# Control.net
KiCad netlist of a schematic drawn in EAGLE
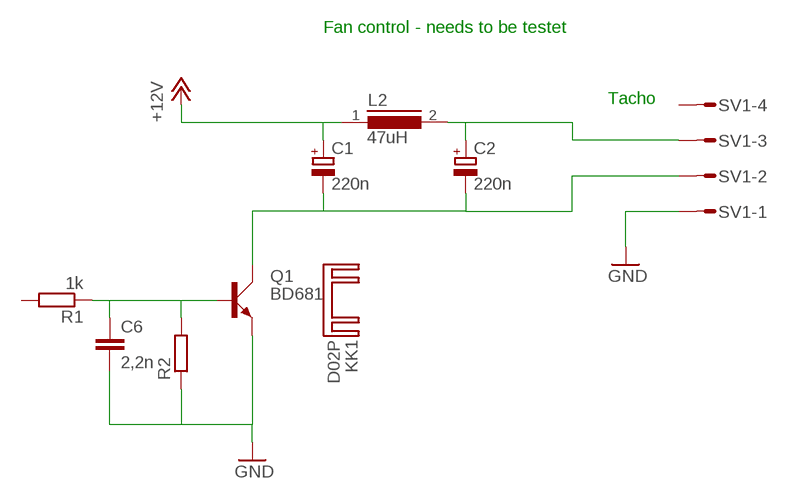
[diagram p0: schematic, sheet 1]

(export (version "E")
  (design (tool "Eeschema 10.0.6"))
  (components
    (comp (ref "C1")
      (value "220n")
      (footprint "eagle-import:E3,5-10")
      (libsource (lib "eagle-import") (part "CPOL-EUE3.5-10"))
    )
    (comp (ref "C2")
      (value "220n")
      (footprint "eagle-import:E3,5-10")
      (libsource (lib "eagle-import") (part "CPOL-EUE3.5-10"))
    )
    (comp (ref "C6")
      (value "2,2n")
      (footprint "eagle-import:C1206")
      (libsource (lib "eagle-import") (part "C-EUC1206"))
    )
    (comp (ref "KK1")
      (value "D02P")
      (footprint "eagle-import:D02PA")
      (libsource (lib "eagle-import") (part "D02P"))
    )
    (comp (ref "L2")
      (value "47uH")
      (footprint "eagle-import:DR125")
      (libsource (lib "eagle-import") (part "DR125"))
    )
    (comp (ref "Q1")
      (value "BD681")
      (footprint "eagle-import:TO126AV")
      (libsource (lib "eagle-import") (part "BD437"))
    )
    (comp (ref "R1")
      (value "1k")
      (footprint "eagle-import:M1206")
      (libsource (lib "eagle-import") (part "R-EU_M1206"))
    )
    (comp (ref "R2")
      (value "R-EU_M1206")
      (footprint "eagle-import:M1206")
      (libsource (lib "eagle-import") (part "R-EU_M1206"))
    )
    (comp (ref "SV1")
      (value "S04P")
      (footprint "eagle-import:S04P")
      (libsource (lib "eagle-import") (part "S04P"))
    )
  )
  (nets
    (net (code "1") (name "+12V") (class "Default")
      (node (ref "C1") (pin "+") (pinfunction "+_+") (pintype "passive"))
      (node (ref "L2") (pin "1") (pinfunction "1_1") (pintype "passive"))
    )
    (net (code "2") (name "GND") (class "Default")
      (node (ref "C6") (pin "2") (pinfunction "2_2") (pintype "passive"))
      (node (ref "Q1") (pin "E") (pinfunction "E_E") (pintype "passive"))
      (node (ref "R2") (pin "1") (pinfunction "1_1") (pintype "passive"))
      (node (ref "SV1") (pin "1") (pinfunction "S_1") (pintype "passive"))
    )
    (net (code "3") (name "Net-(C6-Pad1)") (class "Default")
      (node (ref "C6") (pin "1") (pinfunction "1_1") (pintype "passive"))
      (node (ref "Q1") (pin "B") (pinfunction "B_B") (pintype "passive"))
      (node (ref "R1") (pin "1") (pinfunction "1_1") (pintype "passive"))
      (node (ref "R2") (pin "2") (pinfunction "2_2") (pintype "passive"))
    )
    (net (code "4") (name "Net-(SV1B-S)") (class "Default")
      (node (ref "C1") (pin "-") (pinfunction "-_-") (pintype "passive"))
      (node (ref "C2") (pin "-") (pinfunction "-_-") (pintype "passive"))
      (node (ref "Q1") (pin "C") (pinfunction "C_C") (pintype "passive"))
      (node (ref "SV1") (pin "2") (pinfunction "S_2") (pintype "passive"))
    )
    (net (code "5") (name "Net-(SV1C-S)") (class "Default")
      (node (ref "C2") (pin "+") (pinfunction "+_+") (pintype "passive"))
      (node (ref "L2") (pin "2") (pinfunction "2_2") (pintype "passive"))
      (node (ref "SV1") (pin "3") (pinfunction "S_3") (pintype "passive"))
    )
    (net (code "6") (name "unconnected-(R1-Pad2)") (class "Default")
      (node (ref "R1") (pin "2") (pinfunction "2_2") (pintype "passive"))
    )
    (net (code "7") (name "unconnected-(SV1D-S-Pad4)") (class "Default")
      (node (ref "SV1") (pin "4") (pinfunction "S_4") (pintype "passive"))
    )
  )
)
